# AML166.net
KiCad netlist of a schematic drawn in Altium Designer
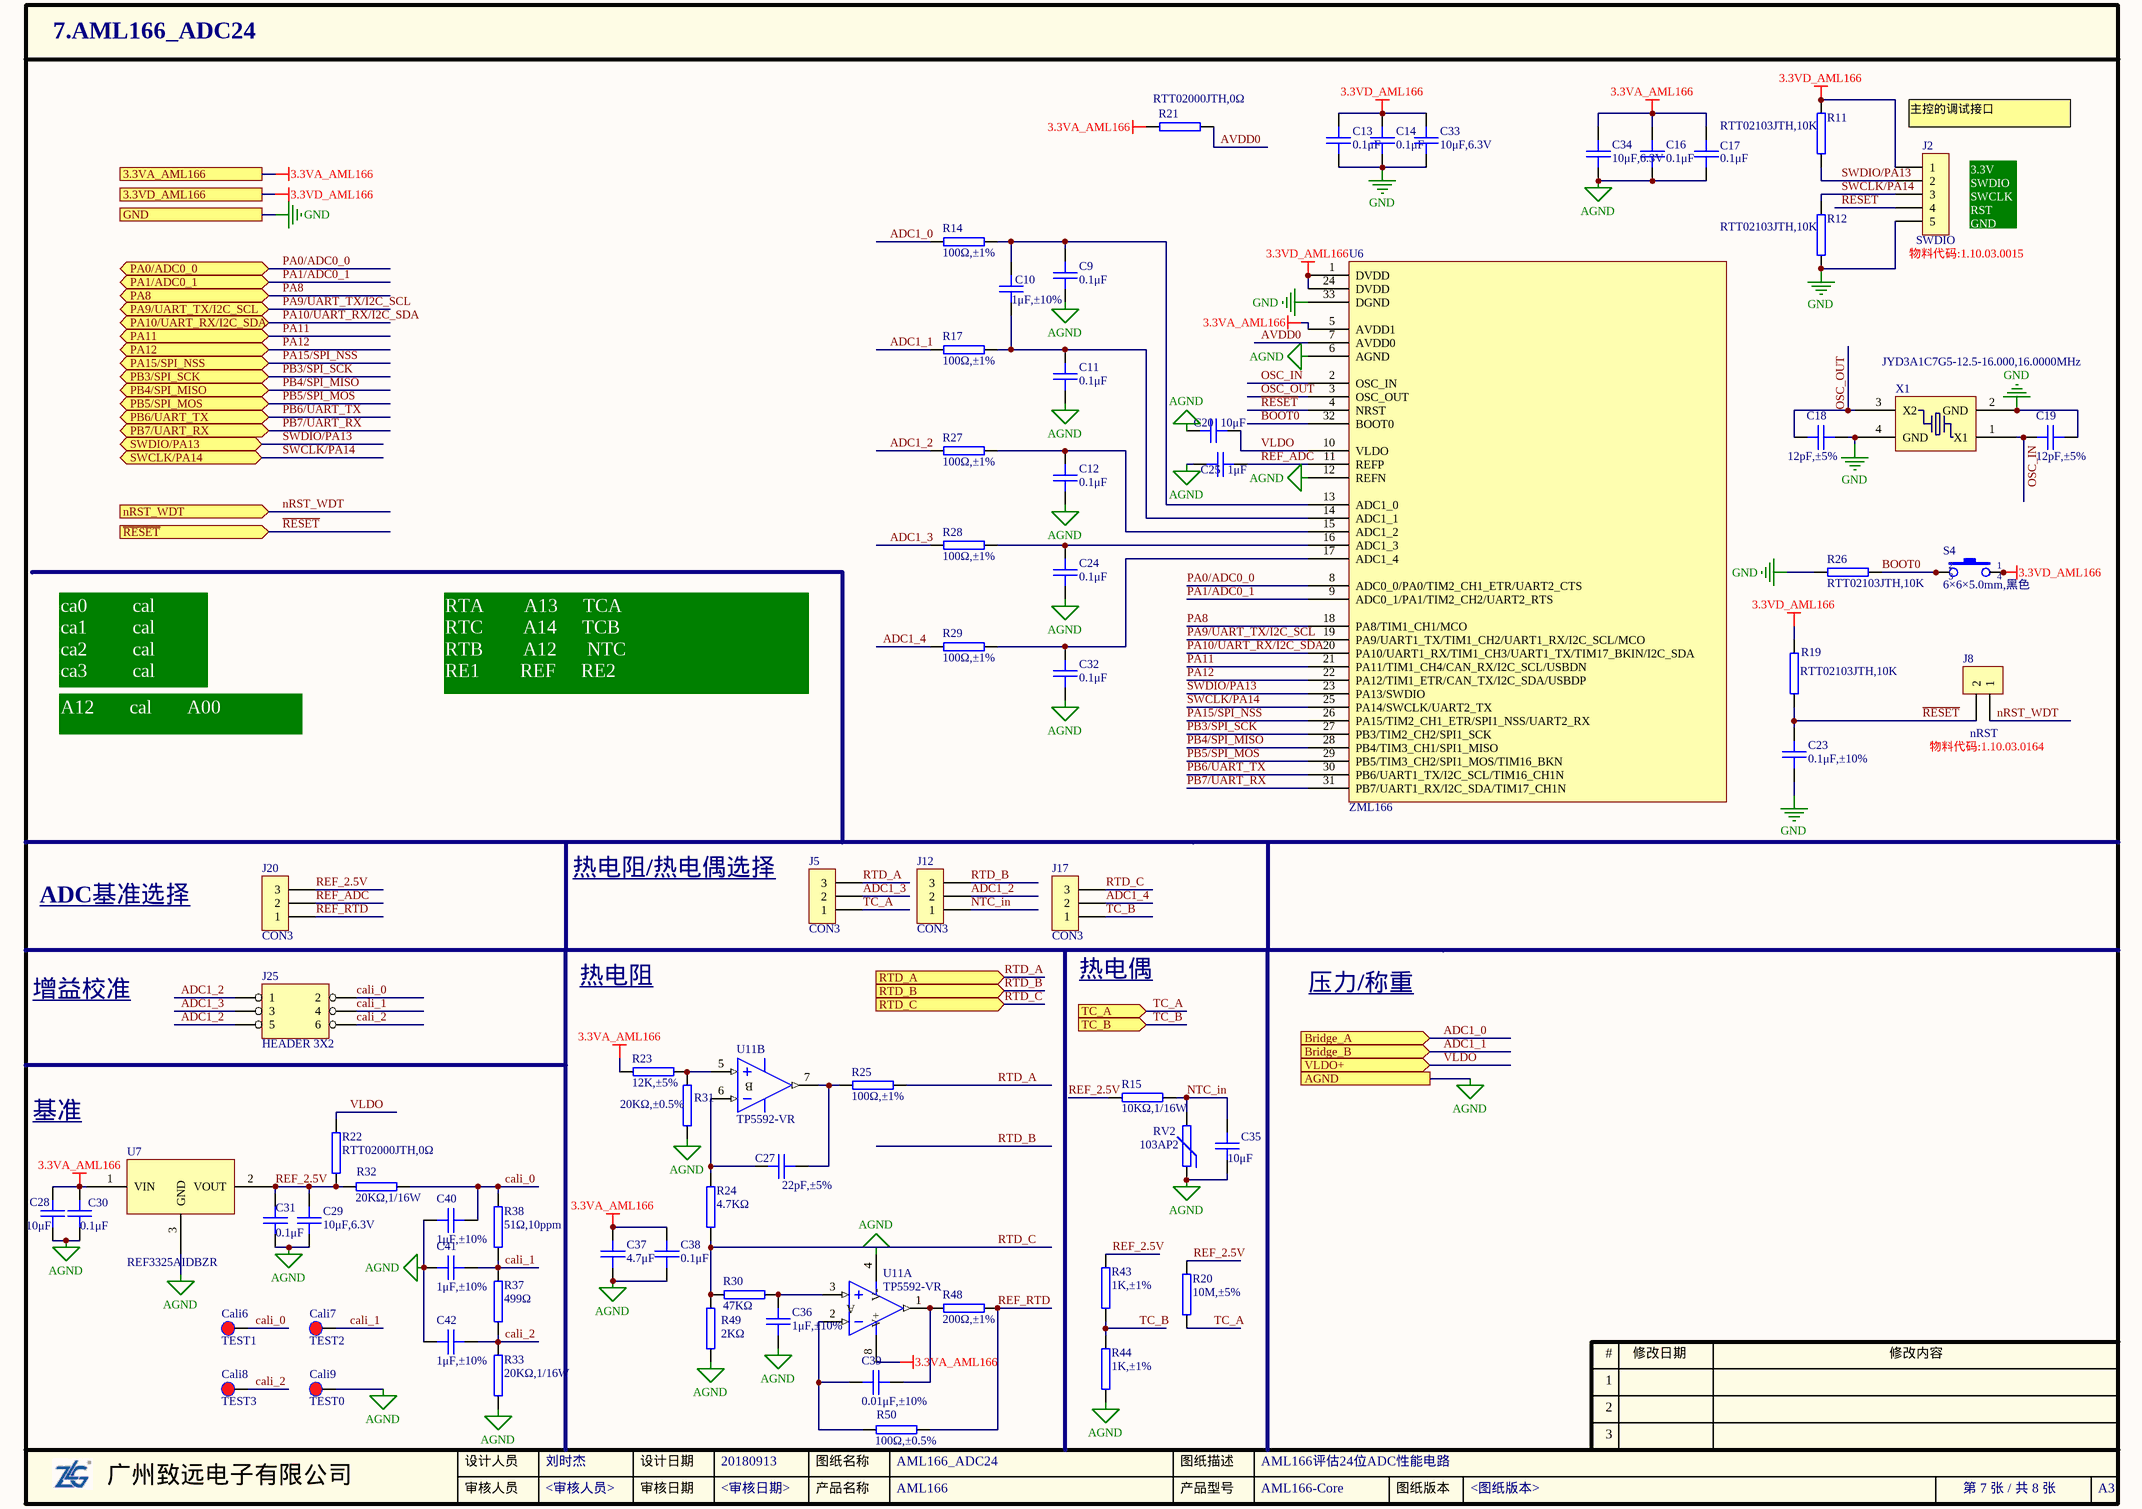
[diagram p0: AML166.SchDoc]

(export (version "E")
  (design (tool "Eeschema 10.0.6"))
  (components
    (comp (ref "C9")
      (value "0.1μF")
      (footprint "0402C")
      (description "GCM155R71E104KE02D,0.1μF,±10%,25V,X7R,0402,muRata,RoHS")
      (libsource (lib "ErpMaterialData") (part "CAP1"))
    )
    (comp (ref "C10")
      (value "1μF,±10%")
      (footprint "0402C")
      (description "GRM155R61C105KA12D,1μF,±10% ,16V,X5R,0402,muRata,RoHS")
      (libsource (lib "ErpMaterialData") (part "CAP1"))
    )
    (comp (ref "C11")
      (value "0.1μF")
      (footprint "0402C")
      (description "GCM155R71E104KE02D,0.1μF,±10%,25V,X7R,0402,muRata,RoHS")
      (libsource (lib "ErpMaterialData") (part "CAP1"))
    )
    (comp (ref "C12")
      (value "0.1μF")
      (footprint "0402C")
      (description "GCM155R71E104KE02D,0.1μF,±10%,25V,X7R,0402,muRata,RoHS")
      (libsource (lib "ErpMaterialData") (part "CAP1"))
    )
    (comp (ref "C13")
      (value "0.1μF")
      (footprint "0402C")
      (description "GCM155R71E104KE02D,0.1μF,±10%,25V,X7R,0402,muRata,RoHS")
      (libsource (lib "ErpMaterialData") (part "CAP1"))
    )
    (comp (ref "C14")
      (value "0.1μF")
      (footprint "0402C")
      (description "GCM155R71E104KE02D,0.1μF,±10%,25V,X7R,0402,muRata,RoHS")
      (libsource (lib "ErpMaterialData") (part "CAP1"))
    )
    (comp (ref "C16")
      (value "0.1μF")
      (footprint "0402C")
      (description "GCM155R71E104KE02D,0.1μF,±10%,25V,X7R,0402,muRata,RoHS")
      (libsource (lib "ErpMaterialData") (part "CAP1"))
    )
    (comp (ref "C17")
      (value "0.1μF")
      (footprint "0402C")
      (description "GCM155R71E104KE02D,0.1μF,±10%,25V,X7R,0402,muRata,RoHS")
      (libsource (lib "ErpMaterialData") (part "CAP1"))
    )
    (comp (ref "C18")
      (value "12pF,±5%")
      (footprint "0402C")
      (description "GRM1555C1H120JA01D,12pF,±5%,50V,C0G,0402,muRata,RoHS")
      (libsource (lib "ErpMaterialData") (part "CAP1"))
    )
    (comp (ref "C19")
      (value "12pF,±5%")
      (footprint "0402C")
      (description "GRM1555C1H120JA01D,12pF,±5%,50V,C0G,0402,muRata,RoHS")
      (libsource (lib "ErpMaterialData") (part "CAP1"))
    )
    (comp (ref "C20")
      (value "10μF")
      (footprint "0603C")
      (description "10μF,6.3V,X5R,GRM188R60J106M****,0603,Murata,RoHS")
      (libsource (lib "ErpMaterialData") (part "CAP1"))
    )
    (comp (ref "C23")
      (value "0.1μF,±10%")
      (footprint "0402C")
      (description "GRM155R71C104KA88D,0.1μF,±10%,16V,X7R,0402,muRata,RoHS")
      (libsource (lib "ErpMaterialData") (part "CAP1"))
    )
    (comp (ref "C24")
      (value "0.1μF")
      (footprint "0402C")
      (description "GCM155R71E104KE02D,0.1μF,±10%,25V,X7R,0402,muRata,RoHS")
      (libsource (lib "ErpMaterialData") (part "CAP1"))
    )
    (comp (ref "C25")
      (value "1μF")
      (footprint "0402C")
      (description "GRM155R61C105KA12D,1μF,±10% ,16V,X5R,0402,muRata,RoHS")
      (libsource (lib "ErpMaterialData") (part "CAP1"))
    )
    (comp (ref "C27")
      (value "22pF,±5%")
      (footprint "0402C")
      (description "GRM1555C1H220JA01D,22pF,±5%,50V,C0G,0402,muRata,RoHS")
      (libsource (lib "ErpMaterialData") (part "CAP1"))
    )
    (comp (ref "C28")
      (value "10μF")
      (footprint "0603C")
      (description "10μF,6.3V,X5R,GRM188R60J106M****,0603,Murata,RoHS")
      (libsource (lib "ErpMaterialData") (part "CAP1"))
    )
    (comp (ref "C29")
      (value "10μF,6.3V")
      (footprint "0603C")
      (description "10μF,6.3V,X5R,GRM188R60J106M****,0603,Murata,RoHS")
      (libsource (lib "ErpMaterialData") (part "CAP1"))
    )
    (comp (ref "C30")
      (value "0.1μF")
      (footprint "0402C")
      (description "GCM155R71E104KE02D,0.1μF,±10%,25V,X7R,0402,muRata,RoHS")
      (libsource (lib "ErpMaterialData") (part "CAP1"))
    )
    (comp (ref "C31")
      (value "0.1μF")
      (footprint "0402C")
      (description "GCM155R71E104KE02D,0.1μF,±10%,25V,X7R,0402,muRata,RoHS")
      (libsource (lib "ErpMaterialData") (part "CAP1"))
    )
    (comp (ref "C32")
      (value "0.1μF")
      (footprint "0402C")
      (description "GCM155R71E104KE02D,0.1μF,±10%,25V,X7R,0402,muRata,RoHS")
      (libsource (lib "ErpMaterialData") (part "CAP1"))
    )
    (comp (ref "C33")
      (value "10μF,6.3V")
      (footprint "0603C")
      (description "10μF,6.3V,X5R,GRM188R60J106M****,0603,Murata,RoHS")
      (libsource (lib "ErpMaterialData") (part "CAP1"))
    )
    (comp (ref "C34")
      (value "10μF,6.3V")
      (footprint "0603C")
      (description "10μF,6.3V,X5R,GRM188R60J106M****,0603,Murata,RoHS")
      (libsource (lib "ErpMaterialData") (part "CAP1"))
    )
    (comp (ref "C35")
      (value "10μF")
      (footprint "0603C")
      (description "10μF,6.3V,X5R,GRM188R60J106M****,0603,Murata,RoHS")
      (libsource (lib "ErpMaterialData") (part "CAP1"))
    )
    (comp (ref "C36")
      (value "1μF,±10%")
      (footprint "0402C")
      (description "GRM155R61C105KA12D,1μF,±10% ,16V,X5R,0402,muRata,RoHS")
      (libsource (lib "ErpMaterialData") (part "CAP1"))
    )
    (comp (ref "C37")
      (value "4.7μF")
      (footprint "0402C")
      (description "GRM155R60J475ME87D,4.7μF,±20%,6.3V,X5R,0402,muRata,RoHS")
      (libsource (lib "ErpMaterialData") (part "CAP1"))
    )
    (comp (ref "C38")
      (value "0.1μF")
      (footprint "0402C")
      (description "GCM155R71E104KE02D,0.1μF,±10%,25V,X7R,0402,muRata,RoHS")
      (libsource (lib "ErpMaterialData") (part "CAP1"))
    )
    (comp (ref "C39")
      (value "0.01μF,±10%")
      (footprint "0402C")
      (description "GRM155R71H103KA88D,0.01μF,±10%,50V,X7R,0402,muRata,RoHS")
      (libsource (lib "ErpMaterialData") (part "CAP1"))
    )
    (comp (ref "C40")
      (value "1μF,±10%")
      (footprint "0402C")
      (description "GRM155R61C105KA12D,1μF,±10% ,16V,X5R,0402,muRata,RoHS")
      (libsource (lib "ErpMaterialData") (part "CAP1"))
    )
    (comp (ref "C41")
      (value "1μF,±10%")
      (footprint "0402C")
      (description "GRM155R61C105KA12D,1μF,±10% ,16V,X5R,0402,muRata,RoHS")
      (libsource (lib "ErpMaterialData") (part "CAP1"))
    )
    (comp (ref "C42")
      (value "1μF,±10%")
      (footprint "0402C")
      (description "GRM155R61C105KA12D,1μF,±10% ,16V,X5R,0402,muRata,RoHS")
      (libsource (lib "ErpMaterialData") (part "CAP1"))
    )
    (comp (ref "Cali6") (value "TEST1") (footprint "PAD-25/40") (libsource (lib "无需物料号元件") (part "TEST-DOT")))
    (comp (ref "Cali7") (value "TEST2") (footprint "PAD-25/40") (libsource (lib "无需物料号元件") (part "TEST-DOT")))
    (comp (ref "Cali8") (value "TEST3") (footprint "PAD-25/40") (libsource (lib "无需物料号元件") (part "TEST-DOT")))
    (comp (ref "Cali9") (value "TEST0") (footprint "PAD-25/40") (libsource (lib "无需物料号元件") (part "TEST-DOT")))
    (comp (ref "J2")
      (value "SWDIO")
      (footprint "SIP-5-2.54-6.0-R90")
      (description "Connector")
      (libsource (lib "无需物料号元件") (part "CON5"))
    )
    (comp (ref "J5")
      (value "CON3")
      (footprint "SIP-3-2.54")
      (description "Connector")
      (libsource (lib "无需物料号元件") (part "CON3"))
    )
    (comp (ref "J8")
      (value "nRST")
      (footprint "SIP-2-2.54")
      (description "Connector")
      (libsource (lib "无需物料号元件") (part "CON2"))
    )
    (comp (ref "J12")
      (value "CON3")
      (footprint "SIP-3-2.54")
      (description "Connector")
      (libsource (lib "无需物料号元件") (part "CON3"))
    )
    (comp (ref "J17")
      (value "CON3")
      (footprint "SIP-3-2.54")
      (description "Connector")
      (libsource (lib "无需物料号元件") (part "CON3"))
    )
    (comp (ref "J20")
      (value "CON3")
      (footprint "SIP-3-2.54")
      (description "Connector")
      (libsource (lib "无需物料号元件") (part "CON3"))
    )
    (comp (ref "J25")
      (value "HEADER 3X2")
      (footprint "IDC-6-2.54")
      (libsource (lib "无需物料号元件") (part "HEADER 3X2"))
    )
    (comp (ref "R11")
      (value "RTT02103JTH,10K")
      (footprint "0402R")
      (description "RTT02103JTH,10K,±5%,0402,RALEC,RoHS")
      (libsource (lib "ErpMaterialData") (part "RES2"))
    )
    (comp (ref "R12")
      (value "RTT02103JTH,10K")
      (footprint "0402R")
      (description "RTT02103JTH,10K,±5%,0402,RALEC,RoHS")
      (libsource (lib "ErpMaterialData") (part "RES2"))
    )
    (comp (ref "R14")
      (value "100Ω,±1%")
      (footprint "0402R")
      (description "100Ω,±1%,0402,RALEC,RoHS")
      (libsource (lib "ErpMaterialData") (part "RES2"))
    )
    (comp (ref "R15")
      (value "10KΩ,1/16W")
      (footprint "0603R")
      (description "10KΩ,1/16W,10PPM/℃,±0.1%,0603,Viking,RoHS")
      (libsource (lib "ErpMaterialData") (part "RES2"))
    )
    (comp (ref "R17")
      (value "100Ω,±1%")
      (footprint "0402R")
      (description "100Ω,±1%,0402,RALEC,RoHS")
      (libsource (lib "ErpMaterialData") (part "RES2"))
    )
    (comp (ref "R19")
      (value "RTT02103JTH,10K")
      (footprint "0402R")
      (description "RTT02103JTH,10K,±5%,0402,RALEC,RoHS")
      (libsource (lib "ErpMaterialData") (part "RES2"))
    )
    (comp (ref "R20")
      (value "10M,±5%")
      (footprint "0402R")
      (description "10M,±5%,0402,RALEC,RoHS")
      (libsource (lib "ErpMaterialData") (part "RES2"))
    )
    (comp (ref "R21")
      (value "RTT02000JTH,0Ω")
      (footprint "0402R")
      (description "RTT02000JTH,0Ω,±5%,0402,RALEC,RoHS")
      (libsource (lib "ErpMaterialData") (part "RES2"))
    )
    (comp (ref "R22")
      (value "RTT02000JTH,0Ω")
      (footprint "0402R")
      (description "RTT02000JTH,0Ω,±5%,0402,RALEC,RoHS")
      (libsource (lib "ErpMaterialData") (part "RES2"))
    )
    (comp (ref "R23")
      (value "12K,±5%")
      (footprint "0402R")
      (description "12K,±5%,0402,RALEC,RoHS")
      (libsource (lib "ErpMaterialData") (part "RES2"))
    )
    (comp (ref "R24")
      (value "4.7KΩ")
      (footprint "0603R")
      (description "4.7KΩ,0603,*,RoHS")
      (libsource (lib "ErpMaterialData") (part "RES2"))
    )
    (comp (ref "R25")
      (value "100Ω,±1%")
      (footprint "0402R")
      (description "100Ω,±1%,0402,RALEC,RoHS")
      (libsource (lib "ErpMaterialData") (part "RES2"))
    )
    (comp (ref "R26")
      (value "RTT02103JTH,10K")
      (footprint "0402R")
      (description "RTT02103JTH,10K,±5%,0402,RALEC,RoHS")
      (libsource (lib "ErpMaterialData") (part "RES2"))
    )
    (comp (ref "R27")
      (value "100Ω,±1%")
      (footprint "0402R")
      (description "100Ω,±1%,0402,RALEC,RoHS")
      (libsource (lib "ErpMaterialData") (part "RES2"))
    )
    (comp (ref "R28")
      (value "100Ω,±1%")
      (footprint "0402R")
      (description "100Ω,±1%,0402,RALEC,RoHS")
      (libsource (lib "ErpMaterialData") (part "RES2"))
    )
    (comp (ref "R29")
      (value "100Ω,±1%")
      (footprint "0402R")
      (description "100Ω,±1%,0402,RALEC,RoHS")
      (libsource (lib "ErpMaterialData") (part "RES2"))
    )
    (comp (ref "R30")
      (value "47KΩ")
      (footprint "0603R")
      (description "47KΩ,0603,*,RoHS")
      (libsource (lib "ErpMaterialData") (part "RES2"))
    )
    (comp (ref "R31")
      (value "20KΩ,±0.5%")
      (footprint "0402R")
      (description "20KΩ,±0.5%,0402,RoHS")
      (libsource (lib "ErpMaterialData") (part "RES2"))
    )
    (comp (ref "R32")
      (value "20KΩ,1/16W")
      (footprint "0603R")
      (description "20KΩ,1/16W,10PPM/℃,±0.1%,0603,Viking,RoHS")
      (libsource (lib "ErpMaterialData") (part "RES2"))
    )
    (comp (ref "R33")
      (value "20KΩ,1/16W")
      (footprint "0603R")
      (description "20KΩ,1/16W,10PPM/℃,±0.1%,0603,Viking,RoHS")
      (libsource (lib "ErpMaterialData") (part "RES2"))
    )
    (comp (ref "R37")
      (value "499Ω")
      (footprint "0603R")
      (description "499Ω,RN731JTTD,4990B10,0603,KOA,RoHS")
      (libsource (lib "ErpMaterialData") (part "RES2"))
    )
    (comp (ref "R38")
      (value "51Ω,10ppm")
      (footprint "0603R")
      (description "51Ω,10ppm,±0.1%,AR03BTB0510,0603,Viking,RoHS")
      (libsource (lib "ErpMaterialData") (part "RES2"))
    )
    (comp (ref "R43")
      (value "1K,±1%")
      (footprint "0402R")
      (description "1K,±1%,0402,RALEC,RoHS")
      (libsource (lib "ErpMaterialData") (part "RES2"))
    )
    (comp (ref "R44")
      (value "1K,±1%")
      (footprint "0402R")
      (description "1K,±1%,0402,RALEC,RoHS")
      (libsource (lib "ErpMaterialData") (part "RES2"))
    )
    (comp (ref "R48")
      (value "200Ω,±1%")
      (footprint "0402R")
      (description "200Ω,±1%,0402,RoHS")
      (libsource (lib "ErpMaterialData") (part "RES2"))
    )
    (comp (ref "R49")
      (value "2KΩ")
      (footprint "0603R")
      (description "2KΩ,RN731JTTD,2001B10,0603,KOA,RoHS")
      (libsource (lib "ErpMaterialData") (part "RES2"))
    )
    (comp (ref "R50")
      (value "100Ω,±0.5%")
      (footprint "0402R")
      (description "100Ω,±0.5%,0402,RoHS")
      (libsource (lib "ErpMaterialData") (part "RES2"))
    )
    (comp (ref "RV2")
      (value "103AP2")
      (footprint "RESRR254W35L380T260H850P")
      (description "103AP2,SIP,semitec,RoHS")
      (libsource (lib "ErpMaterialData") (part "RES4"))
    )
    (comp (ref "S4")
      (value "6×6×5.0mm,黑色")
      (footprint "KEY-6S")
      (description "6×6×5.0mm,黑色,SMD,,*")
      (fields (field (name "Comment") "SW-PB4P"))
      (libsource (lib "ErpMaterialData") (part "SW-PB4P"))
    )
    (comp (ref "U6")
      (value "ZML166")
      (footprint "QFN50P500X500X85-33N")
      (libsource (lib "ZML166") (part "ZML166"))
    )
    (comp (ref "U7")
      (value "REF3325AIDBZR")
      (footprint "SOT-23")
      (description "REF3325AIDBZR,SOT-23,TI")
      (libsource (lib "ErpMaterialData") (part "REF3333"))
    )
    (comp (ref "U11")
      (value "TP5592-VR")
      (footprint "SOP65P490X120-8N")
      (description "TP5592-VR,MSOP-8,3PEAK,RoHS")
      (libsource (lib "ErpMaterialData") (part "TP5592A"))
    )
    (comp (ref "X1")
      (value "JYD3A1C7G5-12.5-16.000,16.0000MHz")
      (footprint "OSCCC250X320X80-4N")
      (description "JYD3A1C7G5-12.5-16.000,16.0000MHz,±10ppm,12.5pF,-40~85℃,SMD3225,JYEG,RoHS")
      (libsource (lib "ErpMaterialData") (part "XTAL4-D"))
    )
  )
  (nets
    (net (code "1") (name "/ADC1_0") (class "Default")
      (node (ref "R14") (pin "1") (pinfunction "1_1") (pintype "passive"))
    )
    (net (code "2") (name "/ADC1_1") (class "Default")
      (node (ref "R17") (pin "1") (pinfunction "1_1") (pintype "passive"))
    )
    (net (code "3") (name "/ADC1_2") (class "Default")
      (node (ref "J12") (pin "2") (pinfunction "2_2") (pintype "passive"))
      (node (ref "J25") (pin "1") (pinfunction "1_1") (pintype "passive"))
      (node (ref "J25") (pin "5") (pinfunction "5_5") (pintype "passive"))
      (node (ref "R27") (pin "1") (pinfunction "1_1") (pintype "passive"))
    )
    (net (code "4") (name "/ADC1_3") (class "Default")
      (node (ref "J25") (pin "3") (pinfunction "3_3") (pintype "passive"))
      (node (ref "J5") (pin "2") (pinfunction "2_2") (pintype "passive"))
      (node (ref "R28") (pin "1") (pinfunction "1_1") (pintype "passive"))
    )
    (net (code "5") (name "/ADC1_4") (class "Default")
      (node (ref "J17") (pin "2") (pinfunction "2_2") (pintype "passive"))
      (node (ref "R29") (pin "1") (pinfunction "1_1") (pintype "passive"))
    )
    (net (code "6") (name "/AVDD0") (class "Default")
      (node (ref "R21") (pin "2") (pinfunction "2_2") (pintype "passive"))
      (node (ref "U6") (pin "7") (pinfunction "AVDD0_7") (pintype "passive"))
    )
    (net (code "7") (name "/BOOT0") (class "Default")
      (node (ref "R26") (pin "1") (pinfunction "1_1") (pintype "passive"))
      (node (ref "S4") (pin "2") (pinfunction "2_2") (pintype "passive"))
      (node (ref "S4") (pin "3") (pinfunction "3_3") (pintype "passive"))
      (node (ref "U6") (pin "32") (pinfunction "BOOT0_32") (pintype "passive"))
    )
    (net (code "8") (name "/NTC_in") (class "Default")
      (node (ref "C35") (pin "2") (pinfunction "2_2") (pintype "passive"))
      (node (ref "J12") (pin "1") (pinfunction "1_1") (pintype "passive"))
      (node (ref "R15") (pin "2") (pinfunction "2_2") (pintype "passive"))
      (node (ref "RV2") (pin "2") (pinfunction "2_2") (pintype "passive"))
    )
    (net (code "9") (name "/OSC_IN") (class "Default")
      (node (ref "C19") (pin "1") (pinfunction "1_1") (pintype "passive"))
      (node (ref "U6") (pin "2") (pinfunction "OSC_IN_2") (pintype "passive"))
      (node (ref "X1") (pin "1") (pinfunction "X1_1") (pintype "passive"))
    )
    (net (code "10") (name "/OSC_OUT") (class "Default")
      (node (ref "C18") (pin "2") (pinfunction "2_2") (pintype "passive"))
      (node (ref "U6") (pin "3") (pinfunction "OSC_OUT_3") (pintype "passive"))
      (node (ref "X1") (pin "3") (pinfunction "X2_3") (pintype "passive"))
    )
    (net (code "11") (name "/PA0{slash}ADC0_0") (class "Default")
      (node (ref "U6") (pin "8") (pinfunction "ADC0_0/PA0/TIM2_CH1_ETR/UART2_CTS_8") (pintype "passive"))
    )
    (net (code "12") (name "/PA1{slash}ADC0_1") (class "Default")
      (node (ref "U6") (pin "9") (pinfunction "ADC0_1/PA1/TIM2_CH2/UART2_RTS_9") (pintype "passive"))
    )
    (net (code "13") (name "/PA8") (class "Default")
      (node (ref "U6") (pin "18") (pinfunction "PA8/TIM1_CH1/MCO_18") (pintype "passive"))
    )
    (net (code "14") (name "/PA9{slash}UART_TX{slash}I2C_SCL") (class "Default")
      (node (ref "U6") (pin "19") (pinfunction "PA9/UART1_TX/TIM1_CH2/UART1_RX/I2C_SCL/MCO_19") (pintype "passive"))
    )
    (net (code "15") (name "/PA10{slash}UART_RX{slash}I2C_SDA") (class "Default")
      (node (ref "U6") (pin "20") (pinfunction "PA10/UART1_RX/TIM1_CH3/UART1_TX/TIM17_BKIN/I2C_SDA_20") (pintype "passive"))
    )
    (net (code "16") (name "/PA11") (class "Default")
      (node (ref "U6") (pin "21") (pinfunction "PA11/TIM1_CH4/CAN_RX/I2C_SCL/USBDN_21") (pintype "passive"))
    )
    (net (code "17") (name "/PA12") (class "Default")
      (node (ref "U6") (pin "22") (pinfunction "PA12/TIM1_ETR/CAN_TX/I2C_SDA/USBDP_22") (pintype "passive"))
    )
    (net (code "18") (name "/PA15{slash}SPI_NSS") (class "Default")
      (node (ref "U6") (pin "26") (pinfunction "PA15/TIM2_CH1_ETR/SPI1_NSS/UART2_RX_26") (pintype "passive"))
    )
    (net (code "19") (name "/PB3{slash}SPI_SCK") (class "Default")
      (node (ref "U6") (pin "27") (pinfunction "PB3/TIM2_CH2/SPI1_SCK_27") (pintype "passive"))
    )
    (net (code "20") (name "/PB4{slash}SPI_MISO") (class "Default")
      (node (ref "U6") (pin "28") (pinfunction "PB4/TIM3_CH1/SPI1_MISO_28") (pintype "passive"))
    )
    (net (code "21") (name "/PB5{slash}SPI_MOS") (class "Default")
      (node (ref "U6") (pin "29") (pinfunction "PB5/TIM3_CH2/SPI1_MOS/TIM16_BKN_29") (pintype "passive"))
    )
    (net (code "22") (name "/PB6{slash}UART_TX") (class "Default")
      (node (ref "U6") (pin "30") (pinfunction "PB6/UART1_TX/I2C_SCL/TIM16_CH1N_30") (pintype "passive"))
    )
    (net (code "23") (name "/PB7{slash}UART_RX") (class "Default")
      (node (ref "U6") (pin "31") (pinfunction "PB7/UART1_RX/I2C_SDA/TIM17_CH1N_31") (pintype "passive"))
    )
    (net (code "24") (name "/REF_2.5V") (class "Default")
      (node (ref "C29") (pin "2") (pinfunction "2_2") (pintype "passive"))
      (node (ref "C31") (pin "1") (pinfunction "1_1") (pintype "passive"))
      (node (ref "J20") (pin "3") (pinfunction "3_3") (pintype "passive"))
      (node (ref "R15") (pin "1") (pinfunction "1_1") (pintype "passive"))
      (node (ref "R20") (pin "2") (pinfunction "2_2") (pintype "passive"))
      (node (ref "R22") (pin "1") (pinfunction "1_1") (pintype "passive"))
      (node (ref "R32") (pin "2") (pinfunction "2_2") (pintype "passive"))
      (node (ref "R43") (pin "2") (pinfunction "2_2") (pintype "passive"))
      (node (ref "U7") (pin "2") (pinfunction "VOUT_2") (pintype "passive"))
    )
    (net (code "25") (name "/REF_ADC") (class "Default")
      (node (ref "C25") (pin "2") (pinfunction "2_2") (pintype "passive"))
      (node (ref "J20") (pin "2") (pinfunction "2_2") (pintype "passive"))
      (node (ref "U6") (pin "11") (pinfunction "REFP_11") (pintype "passive"))
    )
    (net (code "26") (name "/REF_RTD") (class "Default")
      (node (ref "J20") (pin "1") (pinfunction "1_1") (pintype "passive"))
      (node (ref "R48") (pin "2") (pinfunction "2_2") (pintype "passive"))
      (node (ref "R50") (pin "1") (pinfunction "1_1") (pintype "passive"))
    )
    (net (code "27") (name "/RTD_A") (class "Default")
      (node (ref "J5") (pin "3") (pinfunction "3_3") (pintype "passive"))
      (node (ref "R25") (pin "2") (pinfunction "2_2") (pintype "passive"))
    )
    (net (code "28") (name "/RTD_B") (class "Default")
      (node (ref "J12") (pin "3") (pinfunction "3_3") (pintype "passive"))
    )
    (net (code "29") (name "/RTD_C") (class "Default")
      (node (ref "J17") (pin "3") (pinfunction "3_3") (pintype "passive"))
      (node (ref "R24") (pin "1") (pinfunction "1_1") (pintype "passive"))
      (node (ref "R30") (pin "1") (pinfunction "1_1") (pintype "passive"))
      (node (ref "R49") (pin "2") (pinfunction "2_2") (pintype "passive"))
    )
    (net (code "30") (name "/SWCLK{slash}PA14") (class "Default")
      (node (ref "J2") (pin "3") (pinfunction "3_3") (pintype "passive"))
      (node (ref "R12") (pin "2") (pinfunction "2_2") (pintype "passive"))
      (node (ref "U6") (pin "25") (pinfunction "PA14/SWCLK/UART2_TX_25") (pintype "passive"))
    )
    (net (code "31") (name "/SWDIO{slash}PA13") (class "Default")
      (node (ref "J2") (pin "2") (pinfunction "2_2") (pintype "passive"))
      (node (ref "R11") (pin "1") (pinfunction "1_1") (pintype "passive"))
      (node (ref "U6") (pin "23") (pinfunction "PA13/SWDIO_23") (pintype "passive"))
    )
    (net (code "32") (name "/TC_A") (class "Default")
      (node (ref "J5") (pin "1") (pinfunction "1_1") (pintype "passive"))
      (node (ref "R20") (pin "1") (pinfunction "1_1") (pintype "passive"))
    )
    (net (code "33") (name "/TC_B") (class "Default")
      (node (ref "J17") (pin "1") (pinfunction "1_1") (pintype "passive"))
      (node (ref "R43") (pin "1") (pinfunction "1_1") (pintype "passive"))
      (node (ref "R44") (pin "1") (pinfunction "1_1") (pintype "passive"))
    )
    (net (code "34") (name "/VLDO") (class "Default")
      (node (ref "C20") (pin "1") (pinfunction "1_1") (pintype "passive"))
      (node (ref "R22") (pin "2") (pinfunction "2_2") (pintype "passive"))
      (node (ref "U6") (pin "10") (pinfunction "VLDO_10") (pintype "passive"))
    )
    (net (code "35") (name "/cali_0") (class "Default")
      (node (ref "C40") (pin "2") (pinfunction "2_2") (pintype "passive"))
      (node (ref "Cali6") (pin "1") (pinfunction "1_1") (pintype "passive"))
      (node (ref "J25") (pin "2") (pinfunction "2_2") (pintype "passive"))
      (node (ref "R32") (pin "1") (pinfunction "1_1") (pintype "passive"))
      (node (ref "R38") (pin "1") (pinfunction "1_1") (pintype "passive"))
    )
    (net (code "36") (name "/cali_1") (class "Default")
      (node (ref "C41") (pin "2") (pinfunction "2_2") (pintype "passive"))
      (node (ref "Cali7") (pin "1") (pinfunction "1_1") (pintype "passive"))
      (node (ref "J25") (pin "4") (pinfunction "4_4") (pintype "passive"))
      (node (ref "R37") (pin "2") (pinfunction "2_2") (pintype "passive"))
      (node (ref "R38") (pin "2") (pinfunction "2_2") (pintype "passive"))
    )
    (net (code "37") (name "/cali_2") (class "Default")
      (node (ref "C42") (pin "2") (pinfunction "2_2") (pintype "passive"))
      (node (ref "Cali8") (pin "1") (pinfunction "1_1") (pintype "passive"))
      (node (ref "J25") (pin "6") (pinfunction "6_6") (pintype "passive"))
      (node (ref "R33") (pin "1") (pinfunction "1_1") (pintype "passive"))
      (node (ref "R37") (pin "1") (pinfunction "1_1") (pintype "passive"))
    )
    (net (code "38") (name "/nRST_WDT") (class "Default")
      (node (ref "J8") (pin "1") (pinfunction "1_1") (pintype "passive"))
    )
    (net (code "39") (name "/~{RESET}") (class "Default")
      (node (ref "C23") (pin "1") (pinfunction "1_1") (pintype "passive"))
      (node (ref "J2") (pin "4") (pinfunction "4_4") (pintype "passive"))
      (node (ref "J8") (pin "2") (pinfunction "2_2") (pintype "passive"))
      (node (ref "R19") (pin "2") (pinfunction "2_2") (pintype "passive"))
      (node (ref "U6") (pin "4") (pinfunction "NRST_4") (pintype "passive"))
    )
    (net (code "40") (name "3.3VA_AML166") (class "Default")
      (node (ref "C16") (pin "1") (pinfunction "1_1") (pintype "passive"))
      (node (ref "C17") (pin "1") (pinfunction "1_1") (pintype "passive"))
      (node (ref "C28") (pin "2") (pinfunction "2_2") (pintype "passive"))
      (node (ref "C30") (pin "1") (pinfunction "1_1") (pintype "passive"))
      (node (ref "C34") (pin "2") (pinfunction "2_2") (pintype "passive"))
      (node (ref "C37") (pin "1") (pinfunction "1_1") (pintype "passive"))
      (node (ref "C38") (pin "1") (pinfunction "1_1") (pintype "passive"))
      (node (ref "R21") (pin "1") (pinfunction "1_1") (pintype "passive"))
      (node (ref "R23") (pin "1") (pinfunction "1_1") (pintype "passive"))
      (node (ref "U11") (pin "8") (pinfunction "V+_8") (pintype "power_in"))
      (node (ref "U6") (pin "5") (pinfunction "AVDD1_5") (pintype "passive"))
      (node (ref "U7") (pin "1") (pinfunction "VIN_1") (pintype "passive"))
    )
    (net (code "41") (name "3.3VD_AML166") (class "Default")
      (node (ref "C13") (pin "1") (pinfunction "1_1") (pintype "passive"))
      (node (ref "C14") (pin "1") (pinfunction "1_1") (pintype "passive"))
      (node (ref "C33") (pin "2") (pinfunction "2_2") (pintype "passive"))
      (node (ref "J2") (pin "1") (pinfunction "1_1") (pintype "passive"))
      (node (ref "R11") (pin "2") (pinfunction "2_2") (pintype "passive"))
      (node (ref "R19") (pin "1") (pinfunction "1_1") (pintype "passive"))
      (node (ref "S4") (pin "1") (pinfunction "1_1") (pintype "passive"))
      (node (ref "S4") (pin "4") (pinfunction "4_4") (pintype "passive"))
      (node (ref "U6") (pin "1") (pinfunction "DVDD_1") (pintype "passive"))
      (node (ref "U6") (pin "24") (pinfunction "DVDD_24") (pintype "passive"))
    )
    (net (code "42") (name "AGND") (class "Default")
      (node (ref "C11") (pin "2") (pinfunction "2_2") (pintype "passive"))
      (node (ref "C12") (pin "2") (pinfunction "2_2") (pintype "passive"))
      (node (ref "C16") (pin "2") (pinfunction "2_2") (pintype "passive"))
      (node (ref "C17") (pin "2") (pinfunction "2_2") (pintype "passive"))
      (node (ref "C20") (pin "2") (pinfunction "2_2") (pintype "passive"))
      (node (ref "C24") (pin "2") (pinfunction "2_2") (pintype "passive"))
      (node (ref "C25") (pin "1") (pinfunction "1_1") (pintype "passive"))
      (node (ref "C28") (pin "1") (pinfunction "1_1") (pintype "passive"))
      (node (ref "C29") (pin "1") (pinfunction "1_1") (pintype "passive"))
      (node (ref "C30") (pin "2") (pinfunction "2_2") (pintype "passive"))
      (node (ref "C31") (pin "2") (pinfunction "2_2") (pintype "passive"))
      (node (ref "C32") (pin "2") (pinfunction "2_2") (pintype "passive"))
      (node (ref "C34") (pin "1") (pinfunction "1_1") (pintype "passive"))
      (node (ref "C35") (pin "1") (pinfunction "1_1") (pintype "passive"))
      (node (ref "C36") (pin "2") (pinfunction "2_2") (pintype "passive"))
      (node (ref "C37") (pin "2") (pinfunction "2_2") (pintype "passive"))
      (node (ref "C38") (pin "2") (pinfunction "2_2") (pintype "passive"))
      (node (ref "C40") (pin "1") (pinfunction "1_1") (pintype "passive"))
      (node (ref "C41") (pin "1") (pinfunction "1_1") (pintype "passive"))
      (node (ref "C42") (pin "1") (pinfunction "1_1") (pintype "passive"))
      (node (ref "C9") (pin "2") (pinfunction "2_2") (pintype "passive"))
      (node (ref "Cali9") (pin "1") (pinfunction "1_1") (pintype "passive"))
      (node (ref "R31") (pin "1") (pinfunction "1_1") (pintype "passive"))
      (node (ref "R33") (pin "2") (pinfunction "2_2") (pintype "passive"))
      (node (ref "R44") (pin "2") (pinfunction "2_2") (pintype "passive"))
      (node (ref "R49") (pin "1") (pinfunction "1_1") (pintype "passive"))
      (node (ref "RV2") (pin "1") (pinfunction "1_1") (pintype "passive"))
      (node (ref "U11") (pin "4") (pinfunction "V-_4") (pintype "power_in"))
      (node (ref "U6") (pin "12") (pinfunction "REFN_12") (pintype "passive"))
      (node (ref "U6") (pin "6") (pinfunction "AGND_6") (pintype "passive"))
      (node (ref "U7") (pin "3") (pinfunction "GND_3") (pintype "passive"))
    )
    (net (code "43") (name "GND") (class "Default")
      (node (ref "C13") (pin "2") (pinfunction "2_2") (pintype "passive"))
      (node (ref "C14") (pin "2") (pinfunction "2_2") (pintype "passive"))
      (node (ref "C18") (pin "1") (pinfunction "1_1") (pintype "passive"))
      (node (ref "C19") (pin "2") (pinfunction "2_2") (pintype "passive"))
      (node (ref "C23") (pin "2") (pinfunction "2_2") (pintype "passive"))
      (node (ref "C33") (pin "1") (pinfunction "1_1") (pintype "passive"))
      (node (ref "J2") (pin "5") (pinfunction "5_5") (pintype "passive"))
      (node (ref "R12") (pin "1") (pinfunction "1_1") (pintype "passive"))
      (node (ref "R26") (pin "2") (pinfunction "2_2") (pintype "passive"))
      (node (ref "U6") (pin "33") (pinfunction "DGND_33") (pintype "passive"))
      (node (ref "X1") (pin "2") (pinfunction "GND_2") (pintype "passive"))
      (node (ref "X1") (pin "4") (pinfunction "GND_4") (pintype "passive"))
    )
    (net (code "44") (name "Net-(U6-ADC1_0)") (class "Default")
      (node (ref "C10") (pin "1") (pinfunction "1_1") (pintype "passive"))
      (node (ref "C9") (pin "1") (pinfunction "1_1") (pintype "passive"))
      (node (ref "R14") (pin "2") (pinfunction "2_2") (pintype "passive"))
      (node (ref "U6") (pin "13") (pinfunction "ADC1_0_13") (pintype "passive"))
    )
    (net (code "45") (name "Net-(U6-ADC1_1)") (class "Default")
      (node (ref "C10") (pin "2") (pinfunction "2_2") (pintype "passive"))
      (node (ref "C11") (pin "1") (pinfunction "1_1") (pintype "passive"))
      (node (ref "R17") (pin "2") (pinfunction "2_2") (pintype "passive"))
      (node (ref "U6") (pin "14") (pinfunction "ADC1_1_14") (pintype "passive"))
    )
    (net (code "46") (name "Net-(U6-ADC1_2)") (class "Default")
      (node (ref "C12") (pin "1") (pinfunction "1_1") (pintype "passive"))
      (node (ref "R27") (pin "2") (pinfunction "2_2") (pintype "passive"))
      (node (ref "U6") (pin "15") (pinfunction "ADC1_2_15") (pintype "passive"))
    )
    (net (code "47") (name "Net-(U6-ADC1_3)") (class "Default")
      (node (ref "C24") (pin "1") (pinfunction "1_1") (pintype "passive"))
      (node (ref "R28") (pin "2") (pinfunction "2_2") (pintype "passive"))
      (node (ref "U6") (pin "16") (pinfunction "ADC1_3_16") (pintype "passive"))
    )
    (net (code "48") (name "Net-(U6-ADC1_4)") (class "Default")
      (node (ref "C32") (pin "1") (pinfunction "1_1") (pintype "passive"))
      (node (ref "R29") (pin "2") (pinfunction "2_2") (pintype "passive"))
      (node (ref "U6") (pin "17") (pinfunction "ADC1_4_17") (pintype "passive"))
    )
    (net (code "49") (name "Net-(U11A-IN+)") (class "Default")
      (node (ref "C36") (pin "1") (pinfunction "1_1") (pintype "passive"))
      (node (ref "R30") (pin "2") (pinfunction "2_2") (pintype "passive"))
      (node (ref "U11") (pin "3") (pinfunction "IN+_3") (pintype "input"))
    )
    (net (code "50") (name "Net-(U11A-IN-)") (class "Default")
      (node (ref "C39") (pin "1") (pinfunction "1_1") (pintype "passive"))
      (node (ref "R50") (pin "2") (pinfunction "2_2") (pintype "passive"))
      (node (ref "U11") (pin "2") (pinfunction "IN-_2") (pintype "input"))
    )
    (net (code "51") (name "Net-(U11A-OUT)") (class "Default")
      (node (ref "C39") (pin "2") (pinfunction "2_2") (pintype "passive"))
      (node (ref "R48") (pin "1") (pinfunction "1_1") (pintype "passive"))
      (node (ref "U11") (pin "1") (pinfunction "OUT_1") (pintype "output"))
    )
    (net (code "52") (name "Net-(U11B-IN+)") (class "Default")
      (node (ref "R23") (pin "2") (pinfunction "2_2") (pintype "passive"))
      (node (ref "R31") (pin "2") (pinfunction "2_2") (pintype "passive"))
      (node (ref "U11") (pin "5") (pinfunction "IN+_5") (pintype "input"))
    )
    (net (code "53") (name "Net-(U11B-IN-)") (class "Default")
      (node (ref "C27") (pin "1") (pinfunction "1_1") (pintype "passive"))
      (node (ref "R24") (pin "2") (pinfunction "2_2") (pintype "passive"))
      (node (ref "U11") (pin "6") (pinfunction "IN-_6") (pintype "input"))
    )
    (net (code "54") (name "Net-(U11B-OUT)") (class "Default")
      (node (ref "C27") (pin "2") (pinfunction "2_2") (pintype "passive"))
      (node (ref "R25") (pin "1") (pinfunction "1_1") (pintype "passive"))
      (node (ref "U11") (pin "7") (pinfunction "OUT_7") (pintype "output"))
    )
  )
)
